# Main.net
KiCad netlist of a schematic drawn in Altium Designer
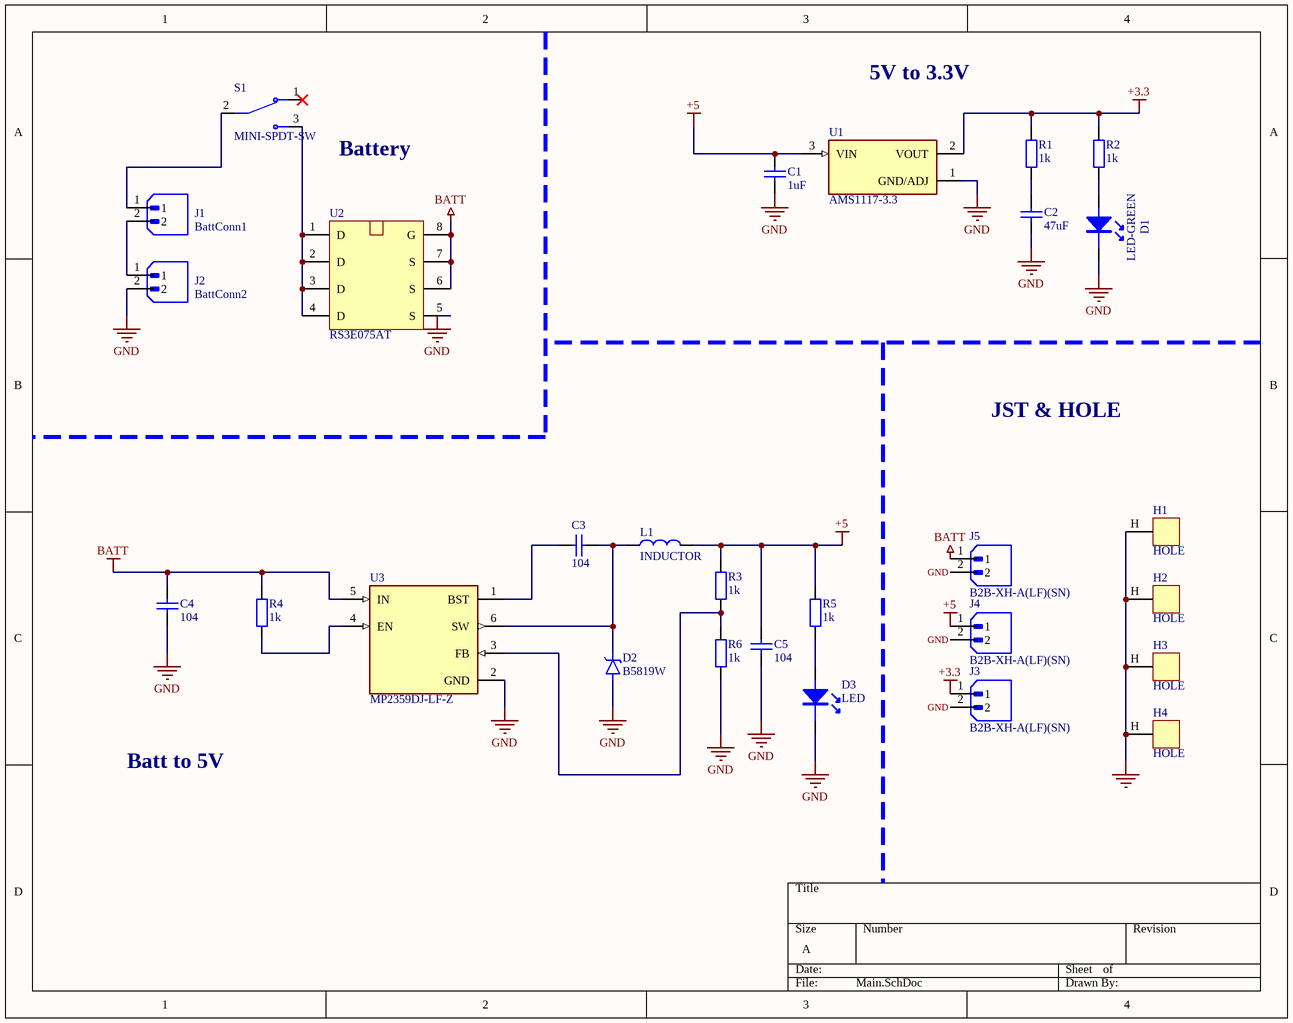
[diagram p0: Main.SchDoc]

(export (version "E")
  (design (tool "Eeschema 10.0.6"))
  (components
    (comp (ref "C1")
      (value "1uF")
      (footprint "CAP_0805")
      (fields (field (name "PUBLISHER") "Altium Limited"))
      (libsource (lib "ThinhNguyenLib") (part "CAP CERAMIC"))
    )
    (comp (ref "C2")
      (value "47uF")
      (footprint "CAP_0805")
      (fields (field (name "PUBLISHER") "Altium Limited"))
      (libsource (lib "ThinhNguyenLib") (part "CAP CERAMIC"))
    )
    (comp (ref "C3")
      (value "104")
      (footprint "0805 CAP")
      (fields (field (name "PUBLISHER") "Altium Limited"))
      (libsource (lib "ThinhNguyenLib") (part "CAP CERAMIC"))
    )
    (comp (ref "C4")
      (value "104")
      (footprint "0805 CAP")
      (fields (field (name "PUBLISHER") "Altium Limited"))
      (libsource (lib "ThinhNguyenLib") (part "CAP CERAMIC"))
    )
    (comp (ref "C5")
      (value "104")
      (footprint "0805 CAP")
      (fields (field (name "PUBLISHER") "Altium Limited"))
      (libsource (lib "ThinhNguyenLib") (part "CAP CERAMIC"))
    )
    (comp (ref "D1")
      (value "LED-GREEN")
      (footprint "LED SMD 0805")
      (libsource (lib "ThinhNguyenLib") (part "LED"))
    )
    (comp (ref "D2")
      (value "B5819W")
      (footprint "SOD-123")
      (fields (field (name "MF") "Taiwan Semiconductor"))
      (libsource (lib "B5819W") (part "B5819W"))
    )
    (comp (ref "D3") (value "LED") (footprint "LED SMD 0805") (libsource (lib "ThinhNguyenLib") (part "LED")))
    (comp (ref "H1") (value "HOLE") (footprint "HOLE") (libsource (lib "ThinhNguyenLib") (part "HOLE")))
    (comp (ref "H2") (value "HOLE") (footprint "HOLE") (libsource (lib "ThinhNguyenLib") (part "HOLE")))
    (comp (ref "H3") (value "HOLE") (footprint "HOLE") (libsource (lib "ThinhNguyenLib") (part "HOLE")))
    (comp (ref "H4") (value "HOLE") (footprint "HOLE") (libsource (lib "ThinhNguyenLib") (part "HOLE")))
    (comp (ref "J1")
      (value "BattConn1")
      (footprint "JST_B2B-XH-A(LF)(SN)")
      (description "Connector Header Through Hole 2 position 0.098 (2.50mm)")
      (fields (field (name "MF") "JST Sales") (field (name "MP") "B2B-XH-A(LF)(SN)"))
      (libsource (lib "B2B-XH-A_LF__SN_") (part "B2B-XH-A(LF)(SN)"))
    )
    (comp (ref "J2")
      (value "BattConn2")
      (footprint "JST_B2B-XH-A(LF)(SN)")
      (description "Connector Header Through Hole 2 position 0.098 (2.50mm)")
      (fields (field (name "MF") "JST Sales") (field (name "MP") "B2B-XH-A(LF)(SN)"))
      (libsource (lib "B2B-XH-A_LF__SN_") (part "B2B-XH-A(LF)(SN)"))
    )
    (comp (ref "J3")
      (value "B2B-XH-A(LF)(SN)")
      (footprint "JST_B2B-XH-A(LF)(SN)")
      (description "Connector Header Through Hole 2 position 0.098 (2.50mm)")
      (fields (field (name "MF") "JST Sales"))
      (libsource (lib "B2B-XH-A_LF__SN_") (part "B2B-XH-A(LF)(SN)"))
    )
    (comp (ref "J4")
      (value "B2B-XH-A(LF)(SN)")
      (footprint "JST_B2B-XH-A(LF)(SN)")
      (description "Connector Header Through Hole 2 position 0.098 (2.50mm)")
      (fields (field (name "MF") "JST Sales"))
      (libsource (lib "B2B-XH-A_LF__SN_") (part "B2B-XH-A(LF)(SN)"))
    )
    (comp (ref "J5")
      (value "B2B-XH-A(LF)(SN)")
      (footprint "JST_B2B-XH-A(LF)(SN)")
      (description "Connector Header Through Hole 2 position 0.098 (2.50mm)")
      (fields (field (name "MF") "JST Sales"))
      (libsource (lib "B2B-XH-A_LF__SN_") (part "B2B-XH-A(LF)(SN)"))
    )
    (comp (ref "L1")
      (value "INDUCTOR")
      (footprint "INDUCTOR 0805")
      (libsource (lib "ThinhNguyenLib") (part "INDUCTOR"))
    )
    (comp (ref "R1") (value "1k") (footprint "RES_0805") (libsource (lib "ThinhNguyenLib") (part "RESISTOR")))
    (comp (ref "R2") (value "1k") (footprint "RES_0805") (libsource (lib "ThinhNguyenLib") (part "RESISTOR")))
    (comp (ref "R3") (value "1k") (footprint "RES_0805") (libsource (lib "ThinhNguyenLib") (part "RESISTOR")))
    (comp (ref "R4") (value "1k") (footprint "RES_0805") (libsource (lib "ThinhNguyenLib") (part "RESISTOR")))
    (comp (ref "R5") (value "1k") (footprint "RES_0805") (libsource (lib "ThinhNguyenLib") (part "RESISTOR")))
    (comp (ref "R6") (value "1k") (footprint "RES_0805") (libsource (lib "ThinhNguyenLib") (part "RESISTOR")))
    (comp (ref "S1")
      (value "MINI-SPDT-SW")
      (footprint "SW_MINI-SPDT-SW")
      (libsource (lib "MINI-SPDT-SW (1)") (part "MINI-SPDT-SW"))
    )
    (comp (ref "U1")
      (value "AMS1117-3.3")
      (footprint "SOT229P700X180-4N")
      (description "Sot223/Pkg 1-Amp 3.3-Volt Low Drop Out Voltage Regulatator")
      (fields (field (name "MF") "Advanced Monolithic Systems"))
      (libsource (lib "AMS1117-3.3") (part "AMS1117-3.3"))
    )
    (comp (ref "U2")
      (value "RS3E075AT")
      (footprint "SOIC 8PIN")
      (libsource (lib "ThinhNguyenLib") (part "L7660"))
    )
    (comp (ref "U3")
      (value "MP2359DJ-LF-Z")
      (footprint "SOT95P280X100-6N")
      (description "Buck Switching Regulator IC Positive Adjustable 0.81V 1 Output 1.2A SOT-23-6 Thin, TSOT-23-6")
      (fields (field (name "MF") "Monolithic Power"))
      (libsource (lib "MP2359DJ-LF-Z") (part "MP2359DJ-LF-Z"))
    )
  )
  (nets
    (net (code "1") (name "+3.3") (class "Default")
      (node (ref "J3") (pin "1") (pinfunction "1_1") (pintype "passive"))
      (node (ref "R1") (pin "2") (pinfunction "2_2") (pintype "passive"))
      (node (ref "R2") (pin "2") (pinfunction "2_2") (pintype "passive"))
      (node (ref "U1") (pin "2") (pinfunction "VOUT_2") (pintype "power_in"))
    )
    (net (code "2") (name "+5") (class "Default")
      (node (ref "C1") (pin "2") (pinfunction "2_2") (pintype "passive"))
      (node (ref "C5") (pin "2") (pinfunction "2_2") (pintype "passive"))
      (node (ref "J4") (pin "1") (pinfunction "1_1") (pintype "passive"))
      (node (ref "L1") (pin "2") (pinfunction "2_2") (pintype "passive"))
      (node (ref "R3") (pin "2") (pinfunction "2_2") (pintype "passive"))
      (node (ref "R5") (pin "2") (pinfunction "2_2") (pintype "passive"))
      (node (ref "U1") (pin "3") (pinfunction "VIN_3") (pintype "input"))
    )
    (net (code "3") (name "BATT") (class "Default")
      (node (ref "C4") (pin "2") (pinfunction "2_2") (pintype "passive"))
      (node (ref "J5") (pin "1") (pinfunction "1_1") (pintype "passive"))
      (node (ref "R4") (pin "2") (pinfunction "2_2") (pintype "passive"))
      (node (ref "U2") (pin "6") (pinfunction "S_6") (pintype "passive"))
      (node (ref "U2") (pin "7") (pinfunction "S_7") (pintype "passive"))
      (node (ref "U2") (pin "8") (pinfunction "G_8") (pintype "passive"))
      (node (ref "U3") (pin "5") (pinfunction "IN_5") (pintype "input"))
    )
    (net (code "4") (name "GND") (class "Default")
      (node (ref "C1") (pin "1") (pinfunction "1_1") (pintype "passive"))
      (node (ref "C2") (pin "1") (pinfunction "1_1") (pintype "passive"))
      (node (ref "C4") (pin "1") (pinfunction "1_1") (pintype "passive"))
      (node (ref "C5") (pin "1") (pinfunction "1_1") (pintype "passive"))
      (node (ref "D1") (pin "2") (pinfunction "2_2") (pintype "passive"))
      (node (ref "D2") (pin "A") (pinfunction "A_A") (pintype "passive"))
      (node (ref "D3") (pin "2") (pinfunction "2_2") (pintype "passive"))
      (node (ref "H1") (pin "H") (pinfunction "HOLE_H") (pintype "passive"))
      (node (ref "H2") (pin "H") (pinfunction "HOLE_H") (pintype "passive"))
      (node (ref "H3") (pin "H") (pinfunction "HOLE_H") (pintype "passive"))
      (node (ref "H4") (pin "H") (pinfunction "HOLE_H") (pintype "passive"))
      (node (ref "J2") (pin "2") (pinfunction "2_2") (pintype "passive"))
      (node (ref "J3") (pin "2") (pinfunction "2_2") (pintype "passive"))
      (node (ref "J4") (pin "2") (pinfunction "2_2") (pintype "passive"))
      (node (ref "J5") (pin "2") (pinfunction "2_2") (pintype "passive"))
      (node (ref "R6") (pin "1") (pinfunction "1_1") (pintype "passive"))
      (node (ref "U1") (pin "1") (pinfunction "GND/ADJ_1") (pintype "power_in"))
      (node (ref "U2") (pin "5") (pinfunction "S_5") (pintype "passive"))
      (node (ref "U3") (pin "2") (pinfunction "GND_2") (pintype "power_in"))
    )
    (net (code "5") (name "Net-(C2-Pad2)") (class "Default")
      (node (ref "C2") (pin "2") (pinfunction "2_2") (pintype "passive"))
      (node (ref "R1") (pin "1") (pinfunction "1_1") (pintype "passive"))
    )
    (net (code "6") (name "Net-(D1-Pad1)") (class "Default")
      (node (ref "D1") (pin "1") (pinfunction "1_1") (pintype "passive"))
      (node (ref "R2") (pin "1") (pinfunction "1_1") (pintype "passive"))
    )
    (net (code "7") (name "Net-(D3-Pad1)") (class "Default")
      (node (ref "D3") (pin "1") (pinfunction "1_1") (pintype "passive"))
      (node (ref "R5") (pin "1") (pinfunction "1_1") (pintype "passive"))
    )
    (net (code "8") (name "Net-(J1-Pad1)") (class "Default")
      (node (ref "J1") (pin "1") (pinfunction "1_1") (pintype "passive"))
      (node (ref "S1") (pin "2") (pinfunction "2_2") (pintype "passive"))
    )
    (net (code "9") (name "Net-(J1-Pad2)") (class "Default")
      (node (ref "J1") (pin "2") (pinfunction "2_2") (pintype "passive"))
      (node (ref "J2") (pin "1") (pinfunction "1_1") (pintype "passive"))
    )
    (net (code "10") (name "Net-(S1-Pad3)") (class "Default")
      (node (ref "S1") (pin "3") (pinfunction "3_3") (pintype "passive"))
      (node (ref "U2") (pin "1") (pinfunction "D_1") (pintype "passive"))
      (node (ref "U2") (pin "2") (pinfunction "D_2") (pintype "passive"))
      (node (ref "U2") (pin "3") (pinfunction "D_3") (pintype "passive"))
      (node (ref "U2") (pin "4") (pinfunction "D_4") (pintype "passive"))
    )
    (net (code "11") (name "Net-(U3-BST)") (class "Default")
      (node (ref "C3") (pin "1") (pinfunction "1_1") (pintype "passive"))
      (node (ref "U3") (pin "1") (pinfunction "BST_1") (pintype "passive"))
    )
    (net (code "12") (name "Net-(U3-EN)") (class "Default")
      (node (ref "R4") (pin "1") (pinfunction "1_1") (pintype "passive"))
      (node (ref "U3") (pin "4") (pinfunction "EN_4") (pintype "input"))
    )
    (net (code "13") (name "Net-(U3-FB)") (class "Default")
      (node (ref "R3") (pin "1") (pinfunction "1_1") (pintype "passive"))
      (node (ref "R6") (pin "2") (pinfunction "2_2") (pintype "passive"))
      (node (ref "U3") (pin "3") (pinfunction "FB_3") (pintype "input"))
    )
    (net (code "14") (name "Net-(U3-SW)") (class "Default")
      (node (ref "C3") (pin "2") (pinfunction "2_2") (pintype "passive"))
      (node (ref "D2") (pin "C") (pinfunction "C_C") (pintype "passive"))
      (node (ref "L1") (pin "1") (pinfunction "1_1") (pintype "passive"))
      (node (ref "U3") (pin "6") (pinfunction "SW_6") (pintype "output"))
    )
    (net (code "15") (name "unconnected-(S1-Pad1)") (class "Default")
      (node (ref "S1") (pin "1") (pinfunction "1_1") (pintype "passive+no_connect"))
    )
  )
)
